# ANALOG_IO.net
KiCad netlist of a schematic drawn in Altium Designer
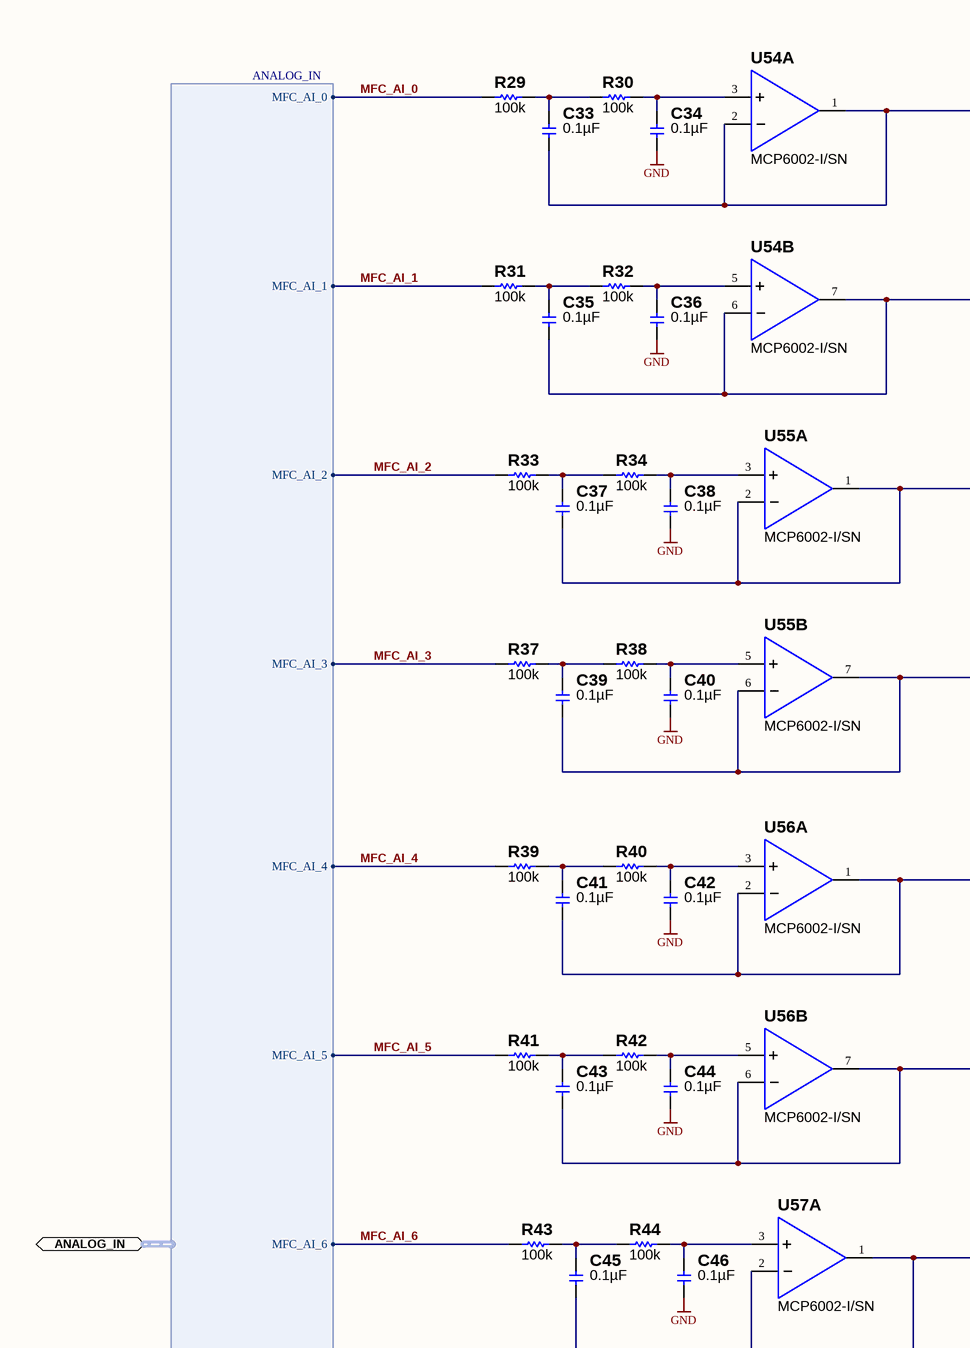
[diagram p0: ANALOG_IO.SchDoc, top left]
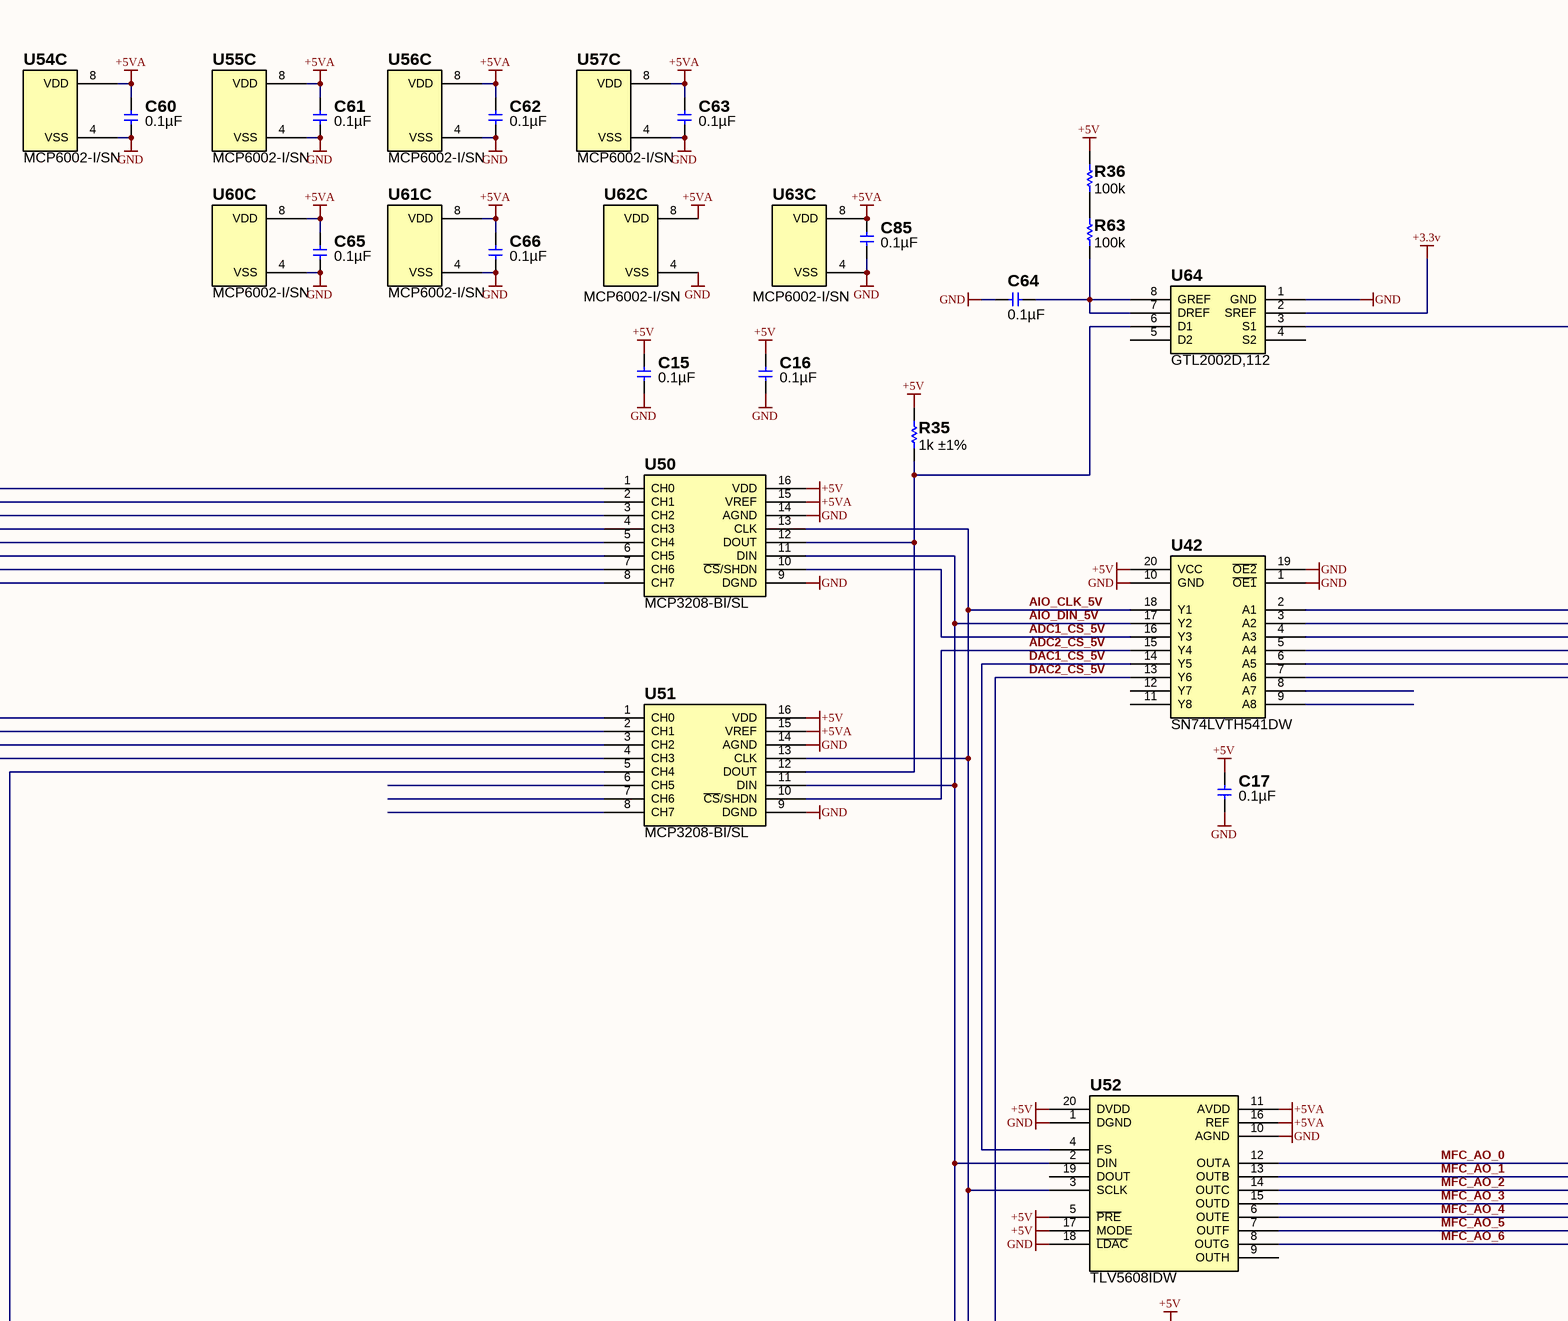
[diagram p1: ANALOG_IO.SchDoc, top middle]
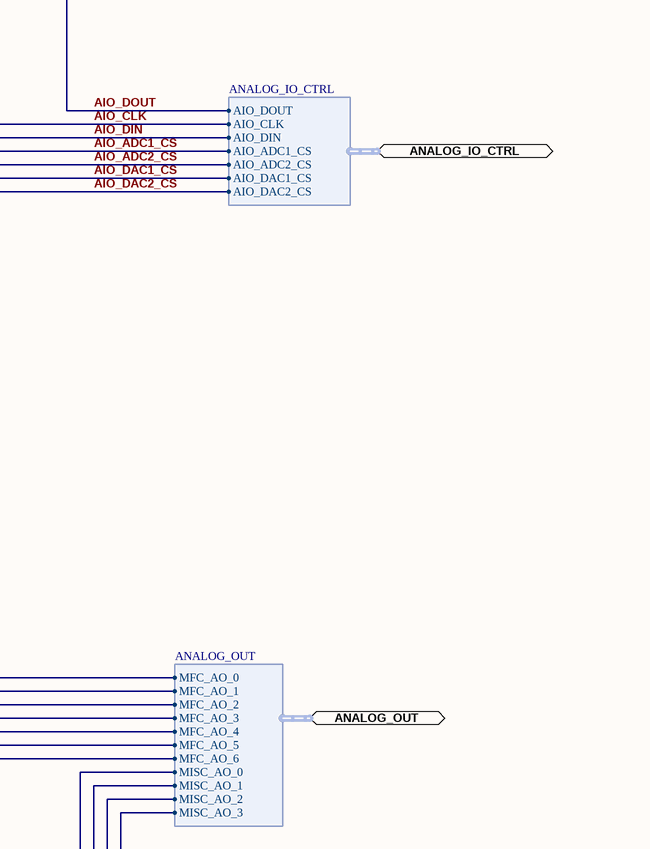
[diagram p2: ANALOG_IO.SchDoc, top right]
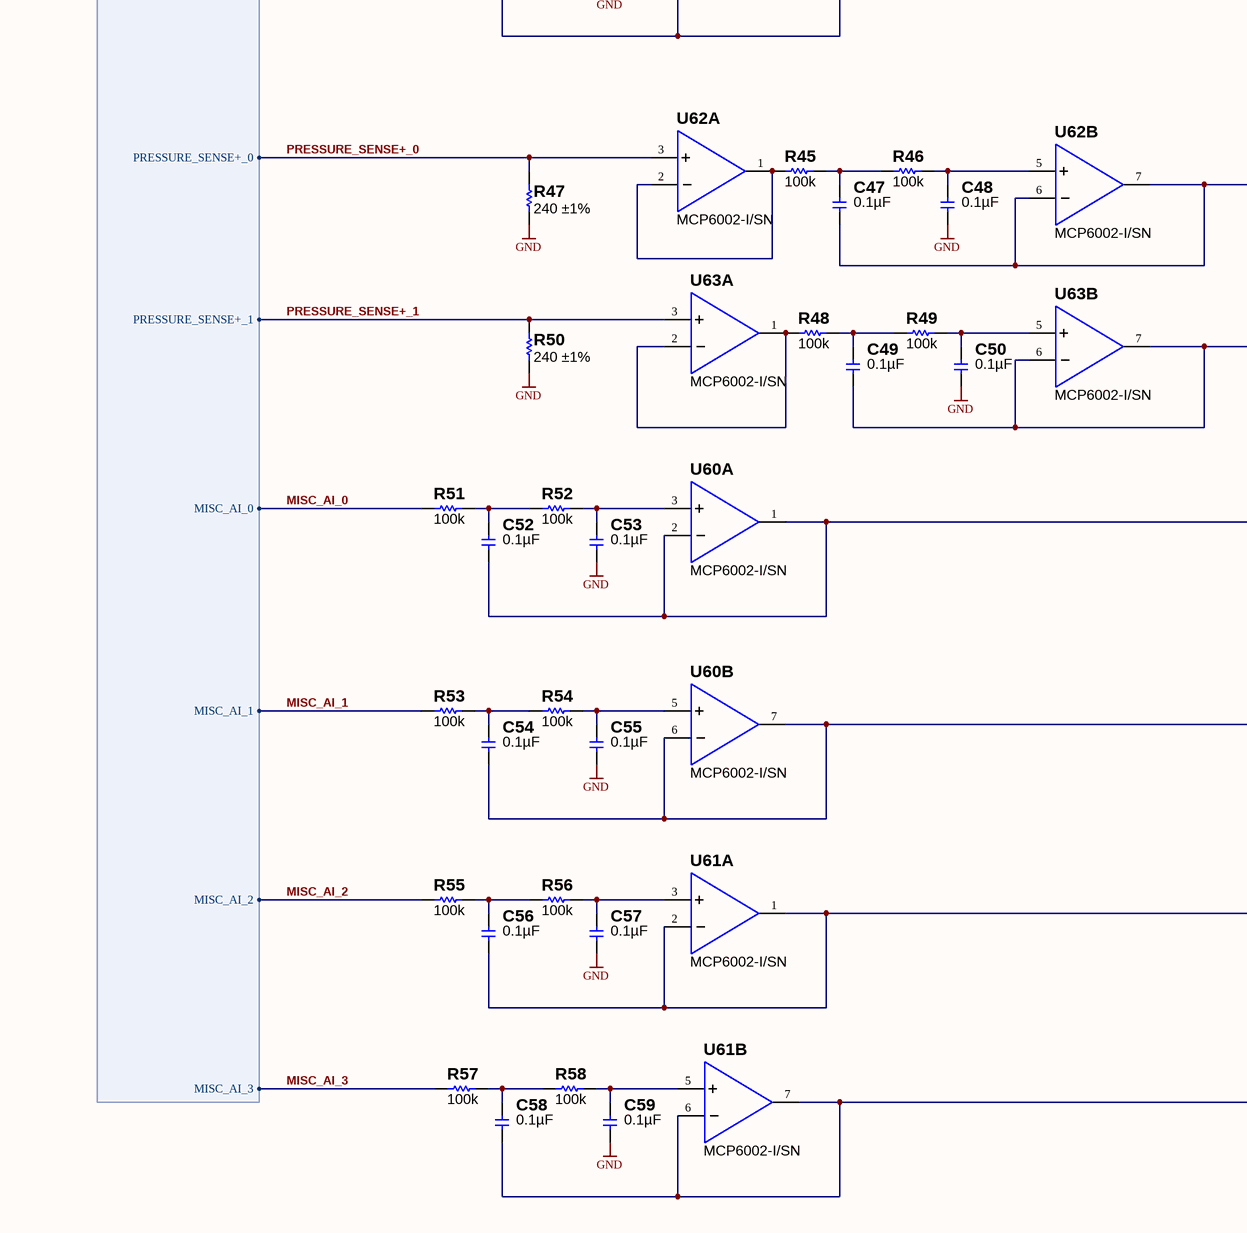
[diagram p3: ANALOG_IO.SchDoc, bottom left]
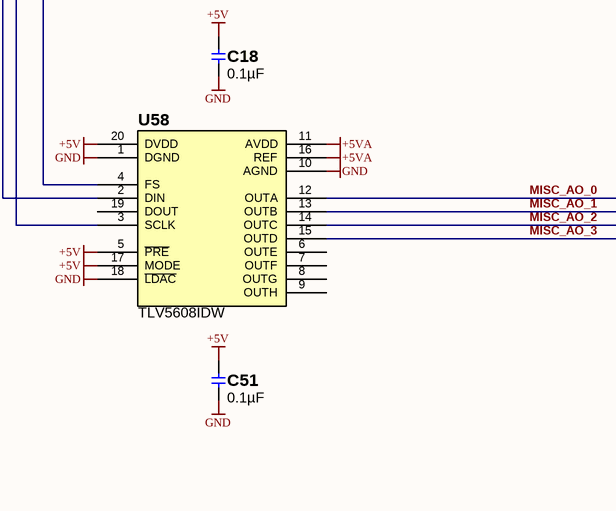
[diagram p4: ANALOG_IO.SchDoc, bottom middle]
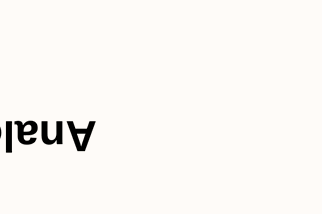
[diagram p5: ANALOG_IO.SchDoc, bottom right]

(export (version "E")
  (design (tool "Eeschema 10.0.6"))
  (components
    (comp (ref "C15")
      (value "0.1µF")
      (footprint "C0805_LD")
      (description "CAP CER 0.1UF 50V 10% X7R 0805")
      (fields
        (field (name "MANUFACTURER PART NUMBER") "GRM21BR71H104KA01L")
        (field (name "MANUFACTURER") "Murata Electronics North America")
      )
      (libsource (lib "Capacitors") (part "C_2P_NP"))
    )
    (comp (ref "C16")
      (value "0.1µF")
      (footprint "C0805_LD")
      (description "CAP CER 0.1UF 50V 10% X7R 0805")
      (fields
        (field (name "MANUFACTURER PART NUMBER") "GRM21BR71H104KA01L")
        (field (name "MANUFACTURER") "Murata Electronics North America")
      )
      (libsource (lib "Capacitors") (part "C_2P_NP"))
    )
    (comp (ref "C17")
      (value "0.1µF")
      (footprint "C0805_LD")
      (description "CAP CER 0.1UF 50V 10% X7R 0805")
      (fields
        (field (name "MANUFACTURER PART NUMBER") "GRM21BR71H104KA01L")
        (field (name "MANUFACTURER") "Murata Electronics North America")
      )
      (libsource (lib "Capacitors") (part "C_2P_NP"))
    )
    (comp (ref "C18")
      (value "0.1µF")
      (footprint "C0805_LD")
      (description "CAP CER 0.1UF 50V 10% X7R 0805")
      (fields
        (field (name "MANUFACTURER PART NUMBER") "GRM21BR71H104KA01L")
        (field (name "MANUFACTURER") "Murata Electronics North America")
      )
      (libsource (lib "Capacitors") (part "C_2P_NP"))
    )
    (comp (ref "C33")
      (value "0.1µF")
      (footprint "C0805_LD")
      (description "CAP CER 0.1UF 50V 10% X7R 0805")
      (fields
        (field (name "MANUFACTURER PART NUMBER") "GRM21BR71H104KA01L")
        (field (name "MANUFACTURER") "Murata Electronics North America")
      )
      (libsource (lib "Capacitors") (part "C_2P_NP"))
    )
    (comp (ref "C34")
      (value "0.1µF")
      (footprint "C0805_LD")
      (description "CAP CER 0.1UF 50V 10% X7R 0805")
      (fields
        (field (name "MANUFACTURER PART NUMBER") "GRM21BR71H104KA01L")
        (field (name "MANUFACTURER") "Murata Electronics North America")
      )
      (libsource (lib "Capacitors") (part "C_2P_NP"))
    )
    (comp (ref "C35")
      (value "0.1µF")
      (footprint "C0805_LD")
      (description "CAP CER 0.1UF 50V 10% X7R 0805")
      (fields
        (field (name "MANUFACTURER PART NUMBER") "GRM21BR71H104KA01L")
        (field (name "MANUFACTURER") "Murata Electronics North America")
      )
      (libsource (lib "Capacitors") (part "C_2P_NP"))
    )
    (comp (ref "C36")
      (value "0.1µF")
      (footprint "C0805_LD")
      (description "CAP CER 0.1UF 50V 10% X7R 0805")
      (fields
        (field (name "MANUFACTURER PART NUMBER") "GRM21BR71H104KA01L")
        (field (name "MANUFACTURER") "Murata Electronics North America")
      )
      (libsource (lib "Capacitors") (part "C_2P_NP"))
    )
    (comp (ref "C37")
      (value "0.1µF")
      (footprint "C0805_LD")
      (description "CAP CER 0.1UF 50V 10% X7R 0805")
      (fields
        (field (name "MANUFACTURER PART NUMBER") "GRM21BR71H104KA01L")
        (field (name "MANUFACTURER") "Murata Electronics North America")
      )
      (libsource (lib "Capacitors") (part "C_2P_NP"))
    )
    (comp (ref "C38")
      (value "0.1µF")
      (footprint "C0805_LD")
      (description "CAP CER 0.1UF 50V 10% X7R 0805")
      (fields
        (field (name "MANUFACTURER PART NUMBER") "GRM21BR71H104KA01L")
        (field (name "MANUFACTURER") "Murata Electronics North America")
      )
      (libsource (lib "Capacitors") (part "C_2P_NP"))
    )
    (comp (ref "C39")
      (value "0.1µF")
      (footprint "C0805_LD")
      (description "CAP CER 0.1UF 50V 10% X7R 0805")
      (fields
        (field (name "MANUFACTURER PART NUMBER") "GRM21BR71H104KA01L")
        (field (name "MANUFACTURER") "Murata Electronics North America")
      )
      (libsource (lib "Capacitors") (part "C_2P_NP"))
    )
    (comp (ref "C40")
      (value "0.1µF")
      (footprint "C0805_LD")
      (description "CAP CER 0.1UF 50V 10% X7R 0805")
      (fields
        (field (name "MANUFACTURER PART NUMBER") "GRM21BR71H104KA01L")
        (field (name "MANUFACTURER") "Murata Electronics North America")
      )
      (libsource (lib "Capacitors") (part "C_2P_NP"))
    )
    (comp (ref "C41")
      (value "0.1µF")
      (footprint "C0805_LD")
      (description "CAP CER 0.1UF 50V 10% X7R 0805")
      (fields
        (field (name "MANUFACTURER PART NUMBER") "GRM21BR71H104KA01L")
        (field (name "MANUFACTURER") "Murata Electronics North America")
      )
      (libsource (lib "Capacitors") (part "C_2P_NP"))
    )
    (comp (ref "C42")
      (value "0.1µF")
      (footprint "C0805_LD")
      (description "CAP CER 0.1UF 50V 10% X7R 0805")
      (fields
        (field (name "MANUFACTURER PART NUMBER") "GRM21BR71H104KA01L")
        (field (name "MANUFACTURER") "Murata Electronics North America")
      )
      (libsource (lib "Capacitors") (part "C_2P_NP"))
    )
    (comp (ref "C43")
      (value "0.1µF")
      (footprint "C0805_LD")
      (description "CAP CER 0.1UF 50V 10% X7R 0805")
      (fields
        (field (name "MANUFACTURER PART NUMBER") "GRM21BR71H104KA01L")
        (field (name "MANUFACTURER") "Murata Electronics North America")
      )
      (libsource (lib "Capacitors") (part "C_2P_NP"))
    )
    (comp (ref "C44")
      (value "0.1µF")
      (footprint "C0805_LD")
      (description "CAP CER 0.1UF 50V 10% X7R 0805")
      (fields
        (field (name "MANUFACTURER PART NUMBER") "GRM21BR71H104KA01L")
        (field (name "MANUFACTURER") "Murata Electronics North America")
      )
      (libsource (lib "Capacitors") (part "C_2P_NP"))
    )
    (comp (ref "C45")
      (value "0.1µF")
      (footprint "C0805_LD")
      (description "CAP CER 0.1UF 50V 10% X7R 0805")
      (fields
        (field (name "MANUFACTURER PART NUMBER") "GRM21BR71H104KA01L")
        (field (name "MANUFACTURER") "Murata Electronics North America")
      )
      (libsource (lib "Capacitors") (part "C_2P_NP"))
    )
    (comp (ref "C46")
      (value "0.1µF")
      (footprint "C0805_LD")
      (description "CAP CER 0.1UF 50V 10% X7R 0805")
      (fields
        (field (name "MANUFACTURER PART NUMBER") "GRM21BR71H104KA01L")
        (field (name "MANUFACTURER") "Murata Electronics North America")
      )
      (libsource (lib "Capacitors") (part "C_2P_NP"))
    )
    (comp (ref "C47")
      (value "0.1µF")
      (footprint "C0805_LD")
      (description "CAP CER 0.1UF 50V 10% X7R 0805")
      (fields
        (field (name "MANUFACTURER PART NUMBER") "GRM21BR71H104KA01L")
        (field (name "MANUFACTURER") "Murata Electronics North America")
      )
      (libsource (lib "Capacitors") (part "C_2P_NP"))
    )
    (comp (ref "C48")
      (value "0.1µF")
      (footprint "C0805_LD")
      (description "CAP CER 0.1UF 50V 10% X7R 0805")
      (fields
        (field (name "MANUFACTURER PART NUMBER") "GRM21BR71H104KA01L")
        (field (name "MANUFACTURER") "Murata Electronics North America")
      )
      (libsource (lib "Capacitors") (part "C_2P_NP"))
    )
    (comp (ref "C49")
      (value "0.1µF")
      (footprint "C0805_LD")
      (description "CAP CER 0.1UF 50V 10% X7R 0805")
      (fields
        (field (name "MANUFACTURER PART NUMBER") "GRM21BR71H104KA01L")
        (field (name "MANUFACTURER") "Murata Electronics North America")
      )
      (libsource (lib "Capacitors") (part "C_2P_NP"))
    )
    (comp (ref "C50")
      (value "0.1µF")
      (footprint "C0805_LD")
      (description "CAP CER 0.1UF 50V 10% X7R 0805")
      (fields
        (field (name "MANUFACTURER PART NUMBER") "GRM21BR71H104KA01L")
        (field (name "MANUFACTURER") "Murata Electronics North America")
      )
      (libsource (lib "Capacitors") (part "C_2P_NP"))
    )
    (comp (ref "C51")
      (value "0.1µF")
      (footprint "C0805_LD")
      (description "CAP CER 0.1UF 50V 10% X7R 0805")
      (fields
        (field (name "MANUFACTURER PART NUMBER") "GRM21BR71H104KA01L")
        (field (name "MANUFACTURER") "Murata Electronics North America")
      )
      (libsource (lib "Capacitors") (part "C_2P_NP"))
    )
    (comp (ref "C52")
      (value "0.1µF")
      (footprint "C0805_LD")
      (description "CAP CER 0.1UF 50V 10% X7R 0805")
      (fields
        (field (name "MANUFACTURER PART NUMBER") "GRM21BR71H104KA01L")
        (field (name "MANUFACTURER") "Murata Electronics North America")
      )
      (libsource (lib "Capacitors") (part "C_2P_NP"))
    )
    (comp (ref "C53")
      (value "0.1µF")
      (footprint "C0805_LD")
      (description "CAP CER 0.1UF 50V 10% X7R 0805")
      (fields
        (field (name "MANUFACTURER PART NUMBER") "GRM21BR71H104KA01L")
        (field (name "MANUFACTURER") "Murata Electronics North America")
      )
      (libsource (lib "Capacitors") (part "C_2P_NP"))
    )
    (comp (ref "C54")
      (value "0.1µF")
      (footprint "C0805_LD")
      (description "CAP CER 0.1UF 50V 10% X7R 0805")
      (fields
        (field (name "MANUFACTURER PART NUMBER") "GRM21BR71H104KA01L")
        (field (name "MANUFACTURER") "Murata Electronics North America")
      )
      (libsource (lib "Capacitors") (part "C_2P_NP"))
    )
    (comp (ref "C55")
      (value "0.1µF")
      (footprint "C0805_LD")
      (description "CAP CER 0.1UF 50V 10% X7R 0805")
      (fields
        (field (name "MANUFACTURER PART NUMBER") "GRM21BR71H104KA01L")
        (field (name "MANUFACTURER") "Murata Electronics North America")
      )
      (libsource (lib "Capacitors") (part "C_2P_NP"))
    )
    (comp (ref "C56")
      (value "0.1µF")
      (footprint "C0805_LD")
      (description "CAP CER 0.1UF 50V 10% X7R 0805")
      (fields
        (field (name "MANUFACTURER PART NUMBER") "GRM21BR71H104KA01L")
        (field (name "MANUFACTURER") "Murata Electronics North America")
      )
      (libsource (lib "Capacitors") (part "C_2P_NP"))
    )
    (comp (ref "C57")
      (value "0.1µF")
      (footprint "C0805_LD")
      (description "CAP CER 0.1UF 50V 10% X7R 0805")
      (fields
        (field (name "MANUFACTURER PART NUMBER") "GRM21BR71H104KA01L")
        (field (name "MANUFACTURER") "Murata Electronics North America")
      )
      (libsource (lib "Capacitors") (part "C_2P_NP"))
    )
    (comp (ref "C58")
      (value "0.1µF")
      (footprint "C0805_LD")
      (description "CAP CER 0.1UF 50V 10% X7R 0805")
      (fields
        (field (name "MANUFACTURER PART NUMBER") "GRM21BR71H104KA01L")
        (field (name "MANUFACTURER") "Murata Electronics North America")
      )
      (libsource (lib "Capacitors") (part "C_2P_NP"))
    )
    (comp (ref "C59")
      (value "0.1µF")
      (footprint "C0805_LD")
      (description "CAP CER 0.1UF 50V 10% X7R 0805")
      (fields
        (field (name "MANUFACTURER PART NUMBER") "GRM21BR71H104KA01L")
        (field (name "MANUFACTURER") "Murata Electronics North America")
      )
      (libsource (lib "Capacitors") (part "C_2P_NP"))
    )
    (comp (ref "C60")
      (value "0.1µF")
      (footprint "C0805_LD")
      (description "CAP CER 0.1UF 50V 10% X7R 0805")
      (fields
        (field (name "MANUFACTURER PART NUMBER") "GRM21BR71H104KA01L")
        (field (name "MANUFACTURER") "Murata Electronics North America")
      )
      (libsource (lib "Capacitors") (part "C_2P_NP"))
    )
    (comp (ref "C61")
      (value "0.1µF")
      (footprint "C0805_LD")
      (description "CAP CER 0.1UF 50V 10% X7R 0805")
      (fields
        (field (name "MANUFACTURER PART NUMBER") "GRM21BR71H104KA01L")
        (field (name "MANUFACTURER") "Murata Electronics North America")
      )
      (libsource (lib "Capacitors") (part "C_2P_NP"))
    )
    (comp (ref "C62")
      (value "0.1µF")
      (footprint "C0805_LD")
      (description "CAP CER 0.1UF 50V 10% X7R 0805")
      (fields
        (field (name "MANUFACTURER PART NUMBER") "GRM21BR71H104KA01L")
        (field (name "MANUFACTURER") "Murata Electronics North America")
      )
      (libsource (lib "Capacitors") (part "C_2P_NP"))
    )
    (comp (ref "C63")
      (value "0.1µF")
      (footprint "C0805_LD")
      (description "CAP CER 0.1UF 50V 10% X7R 0805")
      (fields
        (field (name "MANUFACTURER PART NUMBER") "GRM21BR71H104KA01L")
        (field (name "MANUFACTURER") "Murata Electronics North America")
      )
      (libsource (lib "Capacitors") (part "C_2P_NP"))
    )
    (comp (ref "C64")
      (value "0.1µF")
      (footprint "C0805_LD")
      (description "CAP CER 0.1UF 50V 10% X7R 0805")
      (fields
        (field (name "MANUFACTURER PART NUMBER") "GRM21BR71H104KA01L")
        (field (name "MANUFACTURER") "Murata Electronics North America")
      )
      (libsource (lib "Capacitors") (part "C_2P_NP"))
    )
    (comp (ref "C65")
      (value "0.1µF")
      (footprint "C0805_LD")
      (description "CAP CER 0.1UF 50V 10% X7R 0805")
      (fields
        (field (name "MANUFACTURER PART NUMBER") "GRM21BR71H104KA01L")
        (field (name "MANUFACTURER") "Murata Electronics North America")
      )
      (libsource (lib "Capacitors") (part "C_2P_NP"))
    )
    (comp (ref "C66")
      (value "0.1µF")
      (footprint "C0805_LD")
      (description "CAP CER 0.1UF 50V 10% X7R 0805")
      (fields
        (field (name "MANUFACTURER PART NUMBER") "GRM21BR71H104KA01L")
        (field (name "MANUFACTURER") "Murata Electronics North America")
      )
      (libsource (lib "Capacitors") (part "C_2P_NP"))
    )
    (comp (ref "C85")
      (value "0.1µF")
      (footprint "C0805_LD")
      (description "CAP CER 0.1UF 50V 10% X7R 0805")
      (fields
        (field (name "MANUFACTURER PART NUMBER") "GRM21BR71H104KA01L")
        (field (name "MANUFACTURER") "Murata Electronics North America")
      )
      (libsource (lib "Capacitors") (part "C_2P_NP"))
    )
    (comp (ref "R29")
      (value "100k")
      (footprint "R0805_LD")
      (description "RES 100K OHM 1/8W 1% 0805 SMD")
      (fields
        (field (name "MANUFACTURER PART NUMBER") "ERJ-6ENF1003V")
        (field (name "MANUFACTURER") "Panasonic Electronic Components")
      )
      (libsource (lib "Resistors") (part "R_2P"))
    )
    (comp (ref "R30")
      (value "100k")
      (footprint "R0805_LD")
      (description "RES 100K OHM 1/8W 1% 0805 SMD")
      (fields
        (field (name "MANUFACTURER PART NUMBER") "ERJ-6ENF1003V")
        (field (name "MANUFACTURER") "Panasonic Electronic Components")
      )
      (libsource (lib "Resistors") (part "R_2P"))
    )
    (comp (ref "R31")
      (value "100k")
      (footprint "R0805_LD")
      (description "RES 100K OHM 1/8W 1% 0805 SMD")
      (fields
        (field (name "MANUFACTURER PART NUMBER") "ERJ-6ENF1003V")
        (field (name "MANUFACTURER") "Panasonic Electronic Components")
      )
      (libsource (lib "Resistors") (part "R_2P"))
    )
    (comp (ref "R32")
      (value "100k")
      (footprint "R0805_LD")
      (description "RES 100K OHM 1/8W 1% 0805 SMD")
      (fields
        (field (name "MANUFACTURER PART NUMBER") "ERJ-6ENF1003V")
        (field (name "MANUFACTURER") "Panasonic Electronic Components")
      )
      (libsource (lib "Resistors") (part "R_2P"))
    )
    (comp (ref "R33")
      (value "100k")
      (footprint "R0805_LD")
      (description "RES 100K OHM 1/8W 1% 0805 SMD")
      (fields
        (field (name "MANUFACTURER PART NUMBER") "ERJ-6ENF1003V")
        (field (name "MANUFACTURER") "Panasonic Electronic Components")
      )
      (libsource (lib "Resistors") (part "R_2P"))
    )
    (comp (ref "R34")
      (value "100k")
      (footprint "R0805_LD")
      (description "RES 100K OHM 1/8W 1% 0805 SMD")
      (fields
        (field (name "MANUFACTURER PART NUMBER") "ERJ-6ENF1003V")
        (field (name "MANUFACTURER") "Panasonic Electronic Components")
      )
      (libsource (lib "Resistors") (part "R_2P"))
    )
    (comp (ref "R35")
      (value "1k ±1%")
      (footprint "R0805_LD")
      (description "RES 1K OHM 1/8W 1% 0805 SMD")
      (fields
        (field (name "MANUFACTURER PART NUMBER") "ERJ-6ENF1001V")
        (field (name "MANUFACTURER") "Panasonic Electronic Components")
      )
      (libsource (lib "Resistors") (part "R_2P"))
    )
    (comp (ref "R36")
      (value "100k")
      (footprint "R0805_LD")
      (description "RES 100K OHM 1/8W 1% 0805 SMD")
      (fields
        (field (name "MANUFACTURER PART NUMBER") "ERJ-6ENF1003V")
        (field (name "MANUFACTURER") "Panasonic Electronic Components")
      )
      (libsource (lib "Resistors") (part "R_2P"))
    )
    (comp (ref "R37")
      (value "100k")
      (footprint "R0805_LD")
      (description "RES 100K OHM 1/8W 1% 0805 SMD")
      (fields
        (field (name "MANUFACTURER PART NUMBER") "ERJ-6ENF1003V")
        (field (name "MANUFACTURER") "Panasonic Electronic Components")
      )
      (libsource (lib "Resistors") (part "R_2P"))
    )
    (comp (ref "R38")
      (value "100k")
      (footprint "R0805_LD")
      (description "RES 100K OHM 1/8W 1% 0805 SMD")
      (fields
        (field (name "MANUFACTURER PART NUMBER") "ERJ-6ENF1003V")
        (field (name "MANUFACTURER") "Panasonic Electronic Components")
      )
      (libsource (lib "Resistors") (part "R_2P"))
    )
    (comp (ref "R39")
      (value "100k")
      (footprint "R0805_LD")
      (description "RES 100K OHM 1/8W 1% 0805 SMD")
      (fields
        (field (name "MANUFACTURER PART NUMBER") "ERJ-6ENF1003V")
        (field (name "MANUFACTURER") "Panasonic Electronic Components")
      )
      (libsource (lib "Resistors") (part "R_2P"))
    )
    (comp (ref "R40")
      (value "100k")
      (footprint "R0805_LD")
      (description "RES 100K OHM 1/8W 1% 0805 SMD")
      (fields
        (field (name "MANUFACTURER PART NUMBER") "ERJ-6ENF1003V")
        (field (name "MANUFACTURER") "Panasonic Electronic Components")
      )
      (libsource (lib "Resistors") (part "R_2P"))
    )
    (comp (ref "R41")
      (value "100k")
      (footprint "R0805_LD")
      (description "RES 100K OHM 1/8W 1% 0805 SMD")
      (fields
        (field (name "MANUFACTURER PART NUMBER") "ERJ-6ENF1003V")
        (field (name "MANUFACTURER") "Panasonic Electronic Components")
      )
      (libsource (lib "Resistors") (part "R_2P"))
    )
    (comp (ref "R42")
      (value "100k")
      (footprint "R0805_LD")
      (description "RES 100K OHM 1/8W 1% 0805 SMD")
      (fields
        (field (name "MANUFACTURER PART NUMBER") "ERJ-6ENF1003V")
        (field (name "MANUFACTURER") "Panasonic Electronic Components")
      )
      (libsource (lib "Resistors") (part "R_2P"))
    )
    (comp (ref "R43")
      (value "100k")
      (footprint "R0805_LD")
      (description "RES 100K OHM 1/8W 1% 0805 SMD")
      (fields
        (field (name "MANUFACTURER PART NUMBER") "ERJ-6ENF1003V")
        (field (name "MANUFACTURER") "Panasonic Electronic Components")
      )
      (libsource (lib "Resistors") (part "R_2P"))
    )
    (comp (ref "R44")
      (value "100k")
      (footprint "R0805_LD")
      (description "RES 100K OHM 1/8W 1% 0805 SMD")
      (fields
        (field (name "MANUFACTURER PART NUMBER") "ERJ-6ENF1003V")
        (field (name "MANUFACTURER") "Panasonic Electronic Components")
      )
      (libsource (lib "Resistors") (part "R_2P"))
    )
    (comp (ref "R45")
      (value "100k")
      (footprint "R0805_LD")
      (description "RES 100K OHM 1/8W 1% 0805 SMD")
      (fields
        (field (name "MANUFACTURER PART NUMBER") "ERJ-6ENF1003V")
        (field (name "MANUFACTURER") "Panasonic Electronic Components")
      )
      (libsource (lib "Resistors") (part "R_2P"))
    )
    (comp (ref "R46")
      (value "100k")
      (footprint "R0805_LD")
      (description "RES 100K OHM 1/8W 1% 0805 SMD")
      (fields
        (field (name "MANUFACTURER PART NUMBER") "ERJ-6ENF1003V")
        (field (name "MANUFACTURER") "Panasonic Electronic Components")
      )
      (libsource (lib "Resistors") (part "R_2P"))
    )
    (comp (ref "R47")
      (value "240 ±1%")
      (footprint "R0805_LD")
      (description "RES 240 OHM 1/8W 1% 0805 SMD")
      (fields
        (field (name "MANUFACTURER PART NUMBER") "ERJ-6ENF2400V")
        (field (name "MANUFACTURER") "Panasonic Electronic Components")
      )
      (libsource (lib "Resistors") (part "R_2P"))
    )
    (comp (ref "R48")
      (value "100k")
      (footprint "R0805_LD")
      (description "RES 100K OHM 1/8W 1% 0805 SMD")
      (fields
        (field (name "MANUFACTURER PART NUMBER") "ERJ-6ENF1003V")
        (field (name "MANUFACTURER") "Panasonic Electronic Components")
      )
      (libsource (lib "Resistors") (part "R_2P"))
    )
    (comp (ref "R49")
      (value "100k")
      (footprint "R0805_LD")
      (description "RES 100K OHM 1/8W 1% 0805 SMD")
      (fields
        (field (name "MANUFACTURER PART NUMBER") "ERJ-6ENF1003V")
        (field (name "MANUFACTURER") "Panasonic Electronic Components")
      )
      (libsource (lib "Resistors") (part "R_2P"))
    )
    (comp (ref "R50")
      (value "240 ±1%")
      (footprint "R0805_LD")
      (description "RES 240 OHM 1/8W 1% 0805 SMD")
      (fields
        (field (name "MANUFACTURER PART NUMBER") "ERJ-6ENF2400V")
        (field (name "MANUFACTURER") "Panasonic Electronic Components")
      )
      (libsource (lib "Resistors") (part "R_2P"))
    )
    (comp (ref "R51")
      (value "100k")
      (footprint "R0805_LD")
      (description "RES 100K OHM 1/8W 1% 0805 SMD")
      (fields
        (field (name "MANUFACTURER PART NUMBER") "ERJ-6ENF1003V")
        (field (name "MANUFACTURER") "Panasonic Electronic Components")
      )
      (libsource (lib "Resistors") (part "R_2P"))
    )
    (comp (ref "R52")
      (value "100k")
      (footprint "R0805_LD")
      (description "RES 100K OHM 1/8W 1% 0805 SMD")
      (fields
        (field (name "MANUFACTURER PART NUMBER") "ERJ-6ENF1003V")
        (field (name "MANUFACTURER") "Panasonic Electronic Components")
      )
      (libsource (lib "Resistors") (part "R_2P"))
    )
    (comp (ref "R53")
      (value "100k")
      (footprint "R0805_LD")
      (description "RES 100K OHM 1/8W 1% 0805 SMD")
      (fields
        (field (name "MANUFACTURER PART NUMBER") "ERJ-6ENF1003V")
        (field (name "MANUFACTURER") "Panasonic Electronic Components")
      )
      (libsource (lib "Resistors") (part "R_2P"))
    )
    (comp (ref "R54")
      (value "100k")
      (footprint "R0805_LD")
      (description "RES 100K OHM 1/8W 1% 0805 SMD")
      (fields
        (field (name "MANUFACTURER PART NUMBER") "ERJ-6ENF1003V")
        (field (name "MANUFACTURER") "Panasonic Electronic Components")
      )
      (libsource (lib "Resistors") (part "R_2P"))
    )
    (comp (ref "R55")
      (value "100k")
      (footprint "R0805_LD")
      (description "RES 100K OHM 1/8W 1% 0805 SMD")
      (fields
        (field (name "MANUFACTURER PART NUMBER") "ERJ-6ENF1003V")
        (field (name "MANUFACTURER") "Panasonic Electronic Components")
      )
      (libsource (lib "Resistors") (part "R_2P"))
    )
    (comp (ref "R56")
      (value "100k")
      (footprint "R0805_LD")
      (description "RES 100K OHM 1/8W 1% 0805 SMD")
      (fields
        (field (name "MANUFACTURER PART NUMBER") "ERJ-6ENF1003V")
        (field (name "MANUFACTURER") "Panasonic Electronic Components")
      )
      (libsource (lib "Resistors") (part "R_2P"))
    )
    (comp (ref "R57")
      (value "100k")
      (footprint "R0805_LD")
      (description "RES 100K OHM 1/8W 1% 0805 SMD")
      (fields
        (field (name "MANUFACTURER PART NUMBER") "ERJ-6ENF1003V")
        (field (name "MANUFACTURER") "Panasonic Electronic Components")
      )
      (libsource (lib "Resistors") (part "R_2P"))
    )
    (comp (ref "R58")
      (value "100k")
      (footprint "R0805_LD")
      (description "RES 100K OHM 1/8W 1% 0805 SMD")
      (fields
        (field (name "MANUFACTURER PART NUMBER") "ERJ-6ENF1003V")
        (field (name "MANUFACTURER") "Panasonic Electronic Components")
      )
      (libsource (lib "Resistors") (part "R_2P"))
    )
    (comp (ref "R63")
      (value "100k")
      (footprint "R0805_LD")
      (description "RES 100K OHM 1/8W 1% 0805 SMD")
      (fields
        (field (name "MANUFACTURER PART NUMBER") "ERJ-6ENF1003V")
        (field (name "MANUFACTURER") "Panasonic Electronic Components")
      )
      (libsource (lib "Resistors") (part "R_2P"))
    )
    (comp (ref "U42")
      (value "SN74LVTH541DW")
      (footprint "SOIC127P1030X265-20L")
      (description "IC BUFF/DVR TRI-ST 8BIT 20SOIC")
      (fields (field (name "MANUFACTURER") "Texas Instruments"))
      (libsource (lib "eIC") (part "SN74LVTH541DW"))
    )
    (comp (ref "U50")
      (value "MCP3208-BI/SL")
      (footprint "SOIC127P600X145-16L")
      (description "IC ADC 12BIT 2.7V 8CH SPI 16SOIC")
      (fields (field (name "MANUFACTURER") "Microchip Technology"))
      (libsource (lib "eIC") (part "MCP3208-BI/SL"))
    )
    (comp (ref "U51")
      (value "MCP3208-BI/SL")
      (footprint "SOIC127P600X145-16L")
      (description "IC ADC 12BIT 2.7V 8CH SPI 16SOIC")
      (fields (field (name "MANUFACTURER") "Microchip Technology"))
      (libsource (lib "eIC") (part "MCP3208-BI/SL"))
    )
    (comp (ref "U52")
      (value "TLV5608IDW")
      (footprint "SOIC127P1030X265-20L")
      (description "IC 8 CHANNEL DAC S/O 20-SOIC")
      (fields (field (name "MANUFACTURER") "Texas Instruments"))
      (libsource (lib "eIC") (part "TLV5608IDW"))
    )
    (comp (ref "U54")
      (value "MCP6002-I/SN")
      (footprint "SOIC 8")
      (description "IC OPAMP 1.8V 1MHZ DUAL 8-SOIC")
      (fields (field (name "MANUFACTURER") "Microchip Technology"))
      (libsource (lib "eIC") (part "MCP6002-I/SN"))
    )
    (comp (ref "U55")
      (value "MCP6002-I/SN")
      (footprint "SOIC 8")
      (description "IC OPAMP 1.8V 1MHZ DUAL 8-SOIC")
      (fields (field (name "MANUFACTURER") "Microchip Technology"))
      (libsource (lib "eIC") (part "MCP6002-I/SN"))
    )
    (comp (ref "U56")
      (value "MCP6002-I/SN")
      (footprint "SOIC 8")
      (description "IC OPAMP 1.8V 1MHZ DUAL 8-SOIC")
      (fields (field (name "MANUFACTURER") "Microchip Technology"))
      (libsource (lib "eIC") (part "MCP6002-I/SN"))
    )
    (comp (ref "U57")
      (value "MCP6002-I/SN")
      (footprint "SOIC 8")
      (description "IC OPAMP 1.8V 1MHZ DUAL 8-SOIC")
      (fields (field (name "MANUFACTURER") "Microchip Technology"))
      (libsource (lib "eIC") (part "MCP6002-I/SN"))
    )
    (comp (ref "U58")
      (value "TLV5608IDW")
      (footprint "SOIC127P1030X265-20L")
      (description "IC 8 CHANNEL DAC S/O 20-SOIC")
      (fields (field (name "MANUFACTURER") "Texas Instruments"))
      (libsource (lib "eIC") (part "TLV5608IDW"))
    )
    (comp (ref "U60")
      (value "MCP6002-I/SN")
      (footprint "SOIC 8")
      (description "IC OPAMP 1.8V 1MHZ DUAL 8-SOIC")
      (fields (field (name "MANUFACTURER") "Microchip Technology"))
      (libsource (lib "eIC") (part "MCP6002-I/SN"))
    )
    (comp (ref "U61")
      (value "MCP6002-I/SN")
      (footprint "SOIC 8")
      (description "IC OPAMP 1.8V 1MHZ DUAL 8-SOIC")
      (fields (field (name "MANUFACTURER") "Microchip Technology"))
      (libsource (lib "eIC") (part "MCP6002-I/SN"))
    )
    (comp (ref "U62")
      (value "MCP6002-I/SN")
      (footprint "SOIC 8")
      (description "IC OPAMP 1.8V 1MHZ DUAL 8-SOIC")
      (fields (field (name "MANUFACTURER") "Microchip Technology"))
      (libsource (lib "eIC") (part "MCP6002-I/SN"))
    )
    (comp (ref "U63")
      (value "MCP6002-I/SN")
      (footprint "SOIC 8")
      (description "IC OPAMP 1.8V 1MHZ DUAL 8-SOIC")
      (fields (field (name "MANUFACTURER") "Microchip Technology"))
      (libsource (lib "eIC") (part "MCP6002-I/SN"))
    )
    (comp (ref "U64")
      (value "GTL2002D,112")
      (footprint "SOIC 8")
      (description "IC XLATR 2BIT BI-DIREC 8SOIC")
      (fields (field (name "MANUFACTURER") "NXP Semiconductors"))
      (libsource (lib "eIC") (part "GTL2002D,112"))
    )
  )
  (nets
    (net (code "4") (name "+3.3v") (class "Default")
      (node (ref "U64") (pin "2") (pinfunction "SREF_2") (pintype "passive"))
    )
    (net (code "5") (name "+5V") (class "Default")
      (node (ref "C15") (pin "2") (pinfunction "2_2") (pintype "passive"))
      (node (ref "C16") (pin "2") (pinfunction "2_2") (pintype "passive"))
      (node (ref "C17") (pin "2") (pinfunction "2_2") (pintype "passive"))
      (node (ref "C18") (pin "2") (pinfunction "2_2") (pintype "passive"))
      (node (ref "C51") (pin "2") (pinfunction "2_2") (pintype "passive"))
      (node (ref "R35") (pin "2") (pinfunction "2_2") (pintype "passive"))
      (node (ref "R36") (pin "2") (pinfunction "2_2") (pintype "passive"))
      (node (ref "U42") (pin "20") (pinfunction "VCC_20") (pintype "passive"))
      (node (ref "U50") (pin "16") (pinfunction "VDD_16") (pintype "passive"))
      (node (ref "U51") (pin "16") (pinfunction "VDD_16") (pintype "passive"))
      (node (ref "U52") (pin "17") (pinfunction "MODE_17") (pintype "passive"))
      (node (ref "U52") (pin "20") (pinfunction "DVDD_20") (pintype "passive"))
      (node (ref "U52") (pin "5") (pinfunction "~{PRE}_5") (pintype "passive"))
      (node (ref "U58") (pin "17") (pinfunction "MODE_17") (pintype "passive"))
      (node (ref "U58") (pin "20") (pinfunction "DVDD_20") (pintype "passive"))
      (node (ref "U58") (pin "5") (pinfunction "~{PRE}_5") (pintype "passive"))
    )
    (net (code "6") (name "+5VA") (class "Default")
      (node (ref "C60") (pin "2") (pinfunction "2_2") (pintype "passive"))
      (node (ref "C61") (pin "2") (pinfunction "2_2") (pintype "passive"))
      (node (ref "C62") (pin "2") (pinfunction "2_2") (pintype "passive"))
      (node (ref "C63") (pin "2") (pinfunction "2_2") (pintype "passive"))
      (node (ref "C65") (pin "2") (pinfunction "2_2") (pintype "passive"))
      (node (ref "C66") (pin "2") (pinfunction "2_2") (pintype "passive"))
      (node (ref "C85") (pin "2") (pinfunction "2_2") (pintype "passive"))
      (node (ref "U50") (pin "15") (pinfunction "VREF_15") (pintype "passive"))
      (node (ref "U51") (pin "15") (pinfunction "VREF_15") (pintype "passive"))
      (node (ref "U52") (pin "11") (pinfunction "AVDD_11") (pintype "passive"))
      (node (ref "U52") (pin "16") (pinfunction "REF_16") (pintype "passive"))
      (node (ref "U54") (pin "8") (pinfunction "VDD_8") (pintype "passive"))
      (node (ref "U55") (pin "8") (pinfunction "VDD_8") (pintype "passive"))
      (node (ref "U56") (pin "8") (pinfunction "VDD_8") (pintype "passive"))
      (node (ref "U57") (pin "8") (pinfunction "VDD_8") (pintype "passive"))
      (node (ref "U58") (pin "11") (pinfunction "AVDD_11") (pintype "passive"))
      (node (ref "U58") (pin "16") (pinfunction "REF_16") (pintype "passive"))
      (node (ref "U60") (pin "8") (pinfunction "VDD_8") (pintype "passive"))
      (node (ref "U61") (pin "8") (pinfunction "VDD_8") (pintype "passive"))
      (node (ref "U62") (pin "8") (pinfunction "VDD_8") (pintype "passive"))
      (node (ref "U63") (pin "8") (pinfunction "VDD_8") (pintype "passive"))
    )
    (net (code "7") (name "/ADC1_CS_5V") (class "Default")
      (node (ref "U42") (pin "16") (pinfunction "Y3_16") (pintype "passive"))
      (node (ref "U50") (pin "10") (pinfunction "~{CS}/SHDN_10") (pintype "passive"))
    )
    (net (code "8") (name "/ADC2_CS_5V") (class "Default")
      (node (ref "U42") (pin "15") (pinfunction "Y4_15") (pintype "passive"))
      (node (ref "U51") (pin "10") (pinfunction "~{CS}/SHDN_10") (pintype "passive"))
    )
    (net (code "9") (name "/AIO_ADC1_CS") (class "Default")
      (node (ref "U42") (pin "4") (pinfunction "A3_4") (pintype "passive"))
    )
    (net (code "10") (name "/AIO_ADC2_CS") (class "Default")
      (node (ref "U42") (pin "5") (pinfunction "A4_5") (pintype "passive"))
    )
    (net (code "11") (name "/AIO_CLK") (class "Default")
      (node (ref "U42") (pin "2") (pinfunction "A1_2") (pintype "passive"))
    )
    (net (code "12") (name "/AIO_CLK_5V") (class "Default")
      (node (ref "U42") (pin "18") (pinfunction "Y1_18") (pintype "passive"))
      (node (ref "U50") (pin "13") (pinfunction "CLK_13") (pintype "passive"))
      (node (ref "U51") (pin "13") (pinfunction "CLK_13") (pintype "passive"))
      (node (ref "U52") (pin "3") (pinfunction "SCLK_3") (pintype "passive"))
      (node (ref "U58") (pin "3") (pinfunction "SCLK_3") (pintype "passive"))
    )
    (net (code "13") (name "/AIO_DAC1_CS") (class "Default")
      (node (ref "U42") (pin "6") (pinfunction "A5_6") (pintype "passive"))
    )
    (net (code "14") (name "/AIO_DAC2_CS") (class "Default")
      (node (ref "U42") (pin "7") (pinfunction "A6_7") (pintype "passive"))
    )
    (net (code "15") (name "/AIO_DIN") (class "Default")
      (node (ref "U42") (pin "3") (pinfunction "A2_3") (pintype "passive"))
    )
    (net (code "16") (name "/AIO_DIN_5V") (class "Default")
      (node (ref "U42") (pin "17") (pinfunction "Y2_17") (pintype "passive"))
      (node (ref "U50") (pin "11") (pinfunction "DIN_11") (pintype "passive"))
      (node (ref "U51") (pin "11") (pinfunction "DIN_11") (pintype "passive"))
      (node (ref "U52") (pin "2") (pinfunction "DIN_2") (pintype "passive"))
      (node (ref "U58") (pin "2") (pinfunction "DIN_2") (pintype "passive"))
    )
    (net (code "17") (name "/AIO_DOUT") (class "Default")
      (node (ref "U64") (pin "3") (pinfunction "S1_3") (pintype "passive"))
    )
    (net (code "18") (name "/DAC1_CS_5V") (class "Default")
      (node (ref "U42") (pin "14") (pinfunction "Y5_14") (pintype "passive"))
      (node (ref "U52") (pin "4") (pinfunction "FS_4") (pintype "passive"))
    )
    (net (code "19") (name "/DAC2_CS_5V") (class "Default")
      (node (ref "U42") (pin "13") (pinfunction "Y6_13") (pintype "passive"))
      (node (ref "U58") (pin "4") (pinfunction "FS_4") (pintype "passive"))
    )
    (net (code "20") (name "/MFC_AI_0") (class "Default")
      (node (ref "R29") (pin "1") (pinfunction "1_1") (pintype "passive"))
    )
    (net (code "21") (name "/MFC_AI_1") (class "Default")
      (node (ref "R31") (pin "1") (pinfunction "1_1") (pintype "passive"))
    )
    (net (code "22") (name "/MFC_AI_2") (class "Default")
      (node (ref "R33") (pin "1") (pinfunction "1_1") (pintype "passive"))
    )
    (net (code "23") (name "/MFC_AI_3") (class "Default")
      (node (ref "R37") (pin "1") (pinfunction "1_1") (pintype "passive"))
    )
    (net (code "24") (name "/MFC_AI_4") (class "Default")
      (node (ref "R39") (pin "1") (pinfunction "1_1") (pintype "passive"))
    )
    (net (code "25") (name "/MFC_AI_5") (class "Default")
      (node (ref "R41") (pin "1") (pinfunction "1_1") (pintype "passive"))
    )
    (net (code "26") (name "/MFC_AI_6") (class "Default")
      (node (ref "R43") (pin "1") (pinfunction "1_1") (pintype "passive"))
    )
    (net (code "27") (name "/MFC_AO_0") (class "Default")
      (node (ref "U52") (pin "12") (pinfunction "OUTA_12") (pintype "passive"))
    )
    (net (code "28") (name "/MFC_AO_1") (class "Default")
      (node (ref "U52") (pin "13") (pinfunction "OUTB_13") (pintype "passive"))
    )
    (net (code "29") (name "/MFC_AO_2") (class "Default")
      (node (ref "U52") (pin "14") (pinfunction "OUTC_14") (pintype "passive"))
    )
    (net (code "30") (name "/MFC_AO_3") (class "Default")
      (node (ref "U52") (pin "15") (pinfunction "OUTD_15") (pintype "passive"))
    )
    (net (code "31") (name "/MFC_AO_4") (class "Default")
      (node (ref "U52") (pin "6") (pinfunction "OUTE_6") (pintype "passive"))
    )
    (net (code "32") (name "/MFC_AO_5") (class "Default")
      (node (ref "U52") (pin "7") (pinfunction "OUTF_7") (pintype "passive"))
    )
    (net (code "33") (name "/MFC_AO_6") (class "Default")
      (node (ref "U52") (pin "8") (pinfunction "OUTG_8") (pintype "passive"))
    )
    (net (code "34") (name "/MISC_AI_0") (class "Default")
      (node (ref "R51") (pin "1") (pinfunction "1_1") (pintype "passive"))
    )
    (net (code "35") (name "/MISC_AI_1") (class "Default")
      (node (ref "R53") (pin "1") (pinfunction "1_1") (pintype "passive"))
    )
    (net (code "36") (name "/MISC_AI_2") (class "Default")
      (node (ref "R55") (pin "1") (pinfunction "1_1") (pintype "passive"))
    )
    (net (code "37") (name "/MISC_AI_3") (class "Default")
      (node (ref "R57") (pin "1") (pinfunction "1_1") (pintype "passive"))
    )
    (net (code "38") (name "/MISC_AO_0") (class "Default")
      (node (ref "U58") (pin "12") (pinfunction "OUTA_12") (pintype "passive"))
    )
    (net (code "39") (name "/MISC_AO_1") (class "Default")
      (node (ref "U58") (pin "13") (pinfunction "OUTB_13") (pintype "passive"))
    )
    (net (code "40") (name "/MISC_AO_2") (class "Default")
      (node (ref "U58") (pin "14") (pinfunction "OUTC_14") (pintype "passive"))
    )
    (net (code "41") (name "/MISC_AO_3") (class "Default")
      (node (ref "U58") (pin "15") (pinfunction "OUTD_15") (pintype "passive"))
    )
    (net (code "42") (name "/PRESSURE_SENSE+_0") (class "Default")
      (node (ref "R47") (pin "2") (pinfunction "2_2") (pintype "passive"))
      (node (ref "U62") (pin "3") (pinfunction "+_3") (pintype "passive"))
    )
    (net (code "43") (name "/PRESSURE_SENSE+_1") (class "Default")
      (node (ref "R50") (pin "2") (pinfunction "2_2") (pintype "passive"))
      (node (ref "U63") (pin "3") (pinfunction "+_3") (pintype "passive"))
    )
    (net (code "47") (name "GND") (class "Default")
      (node (ref "C15") (pin "1") (pinfunction "1_1") (pintype "passive"))
      (node (ref "C16") (pin "1") (pinfunction "1_1") (pintype "passive"))
      (node (ref "C17") (pin "1") (pinfunction "1_1") (pintype "passive"))
      (node (ref "C18") (pin "1") (pinfunction "1_1") (pintype "passive"))
      (node (ref "C34") (pin "1") (pinfunction "1_1") (pintype "passive"))
      (node (ref "C36") (pin "1") (pinfunction "1_1") (pintype "passive"))
      (node (ref "C38") (pin "1") (pinfunction "1_1") (pintype "passive"))
      (node (ref "C40") (pin "1") (pinfunction "1_1") (pintype "passive"))
      (node (ref "C42") (pin "1") (pinfunction "1_1") (pintype "passive"))
      (node (ref "C44") (pin "1") (pinfunction "1_1") (pintype "passive"))
      (node (ref "C46") (pin "1") (pinfunction "1_1") (pintype "passive"))
      (node (ref "C48") (pin "1") (pinfunction "1_1") (pintype "passive"))
      (node (ref "C50") (pin "1") (pinfunction "1_1") (pintype "passive"))
      (node (ref "C51") (pin "1") (pinfunction "1_1") (pintype "passive"))
      (node (ref "C53") (pin "1") (pinfunction "1_1") (pintype "passive"))
      (node (ref "C55") (pin "1") (pinfunction "1_1") (pintype "passive"))
      (node (ref "C57") (pin "1") (pinfunction "1_1") (pintype "passive"))
      (node (ref "C59") (pin "1") (pinfunction "1_1") (pintype "passive"))
      (node (ref "C60") (pin "1") (pinfunction "1_1") (pintype "passive"))
      (node (ref "C61") (pin "1") (pinfunction "1_1") (pintype "passive"))
      (node (ref "C62") (pin "1") (pinfunction "1_1") (pintype "passive"))
      (node (ref "C63") (pin "1") (pinfunction "1_1") (pintype "passive"))
      (node (ref "C64") (pin "2") (pinfunction "2_2") (pintype "passive"))
      (node (ref "C65") (pin "1") (pinfunction "1_1") (pintype "passive"))
      (node (ref "C66") (pin "1") (pinfunction "1_1") (pintype "passive"))
      (node (ref "C85") (pin "1") (pinfunction "1_1") (pintype "passive"))
      (node (ref "R47") (pin "1") (pinfunction "1_1") (pintype "passive"))
      (node (ref "R50") (pin "1") (pinfunction "1_1") (pintype "passive"))
      (node (ref "U42") (pin "1") (pinfunction "~{OE1}_1") (pintype "passive"))
      (node (ref "U42") (pin "10") (pinfunction "GND_10") (pintype "passive"))
      (node (ref "U42") (pin "19") (pinfunction "~{OE2}_19") (pintype "passive"))
      (node (ref "U50") (pin "14") (pinfunction "AGND_14") (pintype "passive"))
      (node (ref "U50") (pin "9") (pinfunction "DGND_9") (pintype "passive"))
      (node (ref "U51") (pin "14") (pinfunction "AGND_14") (pintype "passive"))
      (node (ref "U51") (pin "9") (pinfunction "DGND_9") (pintype "passive"))
      (node (ref "U52") (pin "1") (pinfunction "DGND_1") (pintype "passive"))
      (node (ref "U52") (pin "10") (pinfunction "AGND_10") (pintype "passive"))
      (node (ref "U52") (pin "18") (pinfunction "~{LDAC}_18") (pintype "passive"))
      (node (ref "U54") (pin "4") (pinfunction "VSS_4") (pintype "passive"))
      (node (ref "U55") (pin "4") (pinfunction "VSS_4") (pintype "passive"))
      (node (ref "U56") (pin "4") (pinfunction "VSS_4") (pintype "passive"))
      (node (ref "U57") (pin "4") (pinfunction "VSS_4") (pintype "passive"))
      (node (ref "U58") (pin "1") (pinfunction "DGND_1") (pintype "passive"))
      (node (ref "U58") (pin "10") (pinfunction "AGND_10") (pintype "passive"))
      (node (ref "U58") (pin "18") (pinfunction "~{LDAC}_18") (pintype "passive"))
      (node (ref "U60") (pin "4") (pinfunction "VSS_4") (pintype "passive"))
      (node (ref "U61") (pin "4") (pinfunction "VSS_4") (pintype "passive"))
      (node (ref "U62") (pin "4") (pinfunction "VSS_4") (pintype "passive"))
      (node (ref "U63") (pin "4") (pinfunction "VSS_4") (pintype "passive"))
      (node (ref "U64") (pin "1") (pinfunction "GND_1") (pintype "passive"))
    )
    (net (code "48") (name "Net-(C33-Pad2)") (class "Default")
      (node (ref "C33") (pin "2") (pinfunction "2_2") (pintype "passive"))
      (node (ref "R29") (pin "2") (pinfunction "2_2") (pintype "passive"))
      (node (ref "R30") (pin "1") (pinfunction "1_1") (pintype "passive"))
    )
    (net (code "49") (name "Net-(C35-Pad2)") (class "Default")
      (node (ref "C35") (pin "2") (pinfunction "2_2") (pintype "passive"))
      (node (ref "R31") (pin "2") (pinfunction "2_2") (pintype "passive"))
      (node (ref "R32") (pin "1") (pinfunction "1_1") (pintype "passive"))
    )
    (net (code "50") (name "Net-(C37-Pad2)") (class "Default")
      (node (ref "C37") (pin "2") (pinfunction "2_2") (pintype "passive"))
      (node (ref "R33") (pin "2") (pinfunction "2_2") (pintype "passive"))
      (node (ref "R34") (pin "1") (pinfunction "1_1") (pintype "passive"))
    )
    (net (code "51") (name "Net-(C39-Pad2)") (class "Default")
      (node (ref "C39") (pin "2") (pinfunction "2_2") (pintype "passive"))
      (node (ref "R37") (pin "2") (pinfunction "2_2") (pintype "passive"))
      (node (ref "R38") (pin "1") (pinfunction "1_1") (pintype "passive"))
    )
    (net (code "52") (name "Net-(C41-Pad2)") (class "Default")
      (node (ref "C41") (pin "2") (pinfunction "2_2") (pintype "passive"))
      (node (ref "R39") (pin "2") (pinfunction "2_2") (pintype "passive"))
      (node (ref "R40") (pin "1") (pinfunction "1_1") (pintype "passive"))
    )
    (net (code "53") (name "Net-(C43-Pad2)") (class "Default")
      (node (ref "C43") (pin "2") (pinfunction "2_2") (pintype "passive"))
      (node (ref "R41") (pin "2") (pinfunction "2_2") (pintype "passive"))
      (node (ref "R42") (pin "1") (pinfunction "1_1") (pintype "passive"))
    )
    (net (code "54") (name "Net-(C45-Pad2)") (class "Default")
      (node (ref "C45") (pin "2") (pinfunction "2_2") (pintype "passive"))
      (node (ref "R43") (pin "2") (pinfunction "2_2") (pintype "passive"))
      (node (ref "R44") (pin "1") (pinfunction "1_1") (pintype "passive"))
    )
    (net (code "55") (name "Net-(C47-Pad2)") (class "Default")
      (node (ref "C47") (pin "2") (pinfunction "2_2") (pintype "passive"))
      (node (ref "R45") (pin "2") (pinfunction "2_2") (pintype "passive"))
      (node (ref "R46") (pin "1") (pinfunction "1_1") (pintype "passive"))
    )
    (net (code "56") (name "Net-(C49-Pad2)") (class "Default")
      (node (ref "C49") (pin "2") (pinfunction "2_2") (pintype "passive"))
      (node (ref "R48") (pin "2") (pinfunction "2_2") (pintype "passive"))
      (node (ref "R49") (pin "1") (pinfunction "1_1") (pintype "passive"))
    )
    (net (code "57") (name "Net-(C52-Pad2)") (class "Default")
      (node (ref "C52") (pin "2") (pinfunction "2_2") (pintype "passive"))
      (node (ref "R51") (pin "2") (pinfunction "2_2") (pintype "passive"))
      (node (ref "R52") (pin "1") (pinfunction "1_1") (pintype "passive"))
    )
    (net (code "58") (name "Net-(C54-Pad2)") (class "Default")
      (node (ref "C54") (pin "2") (pinfunction "2_2") (pintype "passive"))
      (node (ref "R53") (pin "2") (pinfunction "2_2") (pintype "passive"))
      (node (ref "R54") (pin "1") (pinfunction "1_1") (pintype "passive"))
    )
    (net (code "59") (name "Net-(C56-Pad2)") (class "Default")
      (node (ref "C56") (pin "2") (pinfunction "2_2") (pintype "passive"))
      (node (ref "R55") (pin "2") (pinfunction "2_2") (pintype "passive"))
      (node (ref "R56") (pin "1") (pinfunction "1_1") (pintype "passive"))
    )
    (net (code "60") (name "Net-(C58-Pad2)") (class "Default")
      (node (ref "C58") (pin "2") (pinfunction "2_2") (pintype "passive"))
      (node (ref "R57") (pin "2") (pinfunction "2_2") (pintype "passive"))
      (node (ref "R58") (pin "1") (pinfunction "1_1") (pintype "passive"))
    )
    (net (code "61") (name "Net-(R36-Pad1)") (class "Default")
      (node (ref "R36") (pin "1") (pinfunction "1_1") (pintype "passive"))
      (node (ref "R63") (pin "2") (pinfunction "2_2") (pintype "passive"))
    )
    (net (code "62") (name "Net-(U50-CH0)") (class "Default")
      (node (ref "C33") (pin "1") (pinfunction "1_1") (pintype "passive"))
      (node (ref "U50") (pin "1") (pinfunction "CH0_1") (pintype "passive"))
      (node (ref "U54") (pin "1") (pinfunction "OUT_1") (pintype "passive"))
      (node (ref "U54") (pin "2") (pinfunction "-_2") (pintype "passive"))
    )
    (net (code "63") (name "Net-(U50-CH1)") (class "Default")
      (node (ref "C35") (pin "1") (pinfunction "1_1") (pintype "passive"))
      (node (ref "U50") (pin "2") (pinfunction "CH1_2") (pintype "passive"))
      (node (ref "U54") (pin "6") (pinfunction "-_6") (pintype "passive"))
      (node (ref "U54") (pin "7") (pinfunction "OUT_7") (pintype "passive"))
    )
    (net (code "64") (name "Net-(U50-CH2)") (class "Default")
      (node (ref "C37") (pin "1") (pinfunction "1_1") (pintype "passive"))
      (node (ref "U50") (pin "3") (pinfunction "CH2_3") (pintype "passive"))
      (node (ref "U55") (pin "1") (pinfunction "OUT_1") (pintype "passive"))
      (node (ref "U55") (pin "2") (pinfunction "-_2") (pintype "passive"))
    )
    (net (code "65") (name "Net-(U50-CH3)") (class "Default")
      (node (ref "C39") (pin "1") (pinfunction "1_1") (pintype "passive"))
      (node (ref "U50") (pin "4") (pinfunction "CH3_4") (pintype "passive"))
      (node (ref "U55") (pin "6") (pinfunction "-_6") (pintype "passive"))
      (node (ref "U55") (pin "7") (pinfunction "OUT_7") (pintype "passive"))
    )
    (net (code "66") (name "Net-(U50-CH4)") (class "Default")
      (node (ref "C41") (pin "1") (pinfunction "1_1") (pintype "passive"))
      (node (ref "U50") (pin "5") (pinfunction "CH4_5") (pintype "passive"))
      (node (ref "U56") (pin "1") (pinfunction "OUT_1") (pintype "passive"))
      (node (ref "U56") (pin "2") (pinfunction "-_2") (pintype "passive"))
    )
    (net (code "67") (name "Net-(U50-CH5)") (class "Default")
      (node (ref "C43") (pin "1") (pinfunction "1_1") (pintype "passive"))
      (node (ref "U50") (pin "6") (pinfunction "CH5_6") (pintype "passive"))
      (node (ref "U56") (pin "6") (pinfunction "-_6") (pintype "passive"))
      (node (ref "U56") (pin "7") (pinfunction "OUT_7") (pintype "passive"))
    )
    (net (code "68") (name "Net-(U50-CH6)") (class "Default")
      (node (ref "C45") (pin "1") (pinfunction "1_1") (pintype "passive"))
      (node (ref "U50") (pin "7") (pinfunction "CH6_7") (pintype "passive"))
      (node (ref "U57") (pin "1") (pinfunction "OUT_1") (pintype "passive"))
      (node (ref "U57") (pin "2") (pinfunction "-_2") (pintype "passive"))
    )
    (net (code "69") (name "Net-(U50-CH7)") (class "Default")
      (node (ref "C47") (pin "1") (pinfunction "1_1") (pintype "passive"))
      (node (ref "U50") (pin "8") (pinfunction "CH7_8") (pintype "passive"))
      (node (ref "U62") (pin "6") (pinfunction "-_6") (pintype "passive"))
      (node (ref "U62") (pin "7") (pinfunction "OUT_7") (pintype "passive"))
    )
    (net (code "70") (name "Net-(U50-DOUT)") (class "Default")
      (node (ref "R35") (pin "1") (pinfunction "1_1") (pintype "passive"))
      (node (ref "U50") (pin "12") (pinfunction "DOUT_12") (pintype "passive"))
      (node (ref "U51") (pin "12") (pinfunction "DOUT_12") (pintype "passive"))
      (node (ref "U64") (pin "6") (pinfunction "D1_6") (pintype "passive"))
    )
    (net (code "71") (name "Net-(U51-CH0)") (class "Default")
      (node (ref "C49") (pin "1") (pinfunction "1_1") (pintype "passive"))
      (node (ref "U51") (pin "1") (pinfunction "CH0_1") (pintype "passive"))
      (node (ref "U63") (pin "6") (pinfunction "-_6") (pintype "passive"))
      (node (ref "U63") (pin "7") (pinfunction "OUT_7") (pintype "passive"))
    )
    (net (code "72") (name "Net-(U51-CH1)") (class "Default")
      (node (ref "C52") (pin "1") (pinfunction "1_1") (pintype "passive"))
      (node (ref "U51") (pin "2") (pinfunction "CH1_2") (pintype "passive"))
      (node (ref "U60") (pin "1") (pinfunction "OUT_1") (pintype "passive"))
      (node (ref "U60") (pin "2") (pinfunction "-_2") (pintype "passive"))
    )
    (net (code "73") (name "Net-(U51-CH2)") (class "Default")
      (node (ref "C54") (pin "1") (pinfunction "1_1") (pintype "passive"))
      (node (ref "U51") (pin "3") (pinfunction "CH2_3") (pintype "passive"))
      (node (ref "U60") (pin "6") (pinfunction "-_6") (pintype "passive"))
      (node (ref "U60") (pin "7") (pinfunction "OUT_7") (pintype "passive"))
    )
    (net (code "74") (name "Net-(U51-CH3)") (class "Default")
      (node (ref "C56") (pin "1") (pinfunction "1_1") (pintype "passive"))
      (node (ref "U51") (pin "4") (pinfunction "CH3_4") (pintype "passive"))
      (node (ref "U61") (pin "1") (pinfunction "OUT_1") (pintype "passive"))
      (node (ref "U61") (pin "2") (pinfunction "-_2") (pintype "passive"))
    )
    (net (code "75") (name "Net-(U51-CH4)") (class "Default")
      (node (ref "C58") (pin "1") (pinfunction "1_1") (pintype "passive"))
      (node (ref "U51") (pin "5") (pinfunction "CH4_5") (pintype "passive"))
      (node (ref "U61") (pin "6") (pinfunction "-_6") (pintype "passive"))
      (node (ref "U61") (pin "7") (pinfunction "OUT_7") (pintype "passive"))
    )
    (net (code "76") (name "Net-(U54A-+)") (class "Default")
      (node (ref "C34") (pin "2") (pinfunction "2_2") (pintype "passive"))
      (node (ref "R30") (pin "2") (pinfunction "2_2") (pintype "passive"))
      (node (ref "U54") (pin "3") (pinfunction "+_3") (pintype "passive"))
    )
    (net (code "77") (name "Net-(U54B-+)") (class "Default")
      (node (ref "C36") (pin "2") (pinfunction "2_2") (pintype "passive"))
      (node (ref "R32") (pin "2") (pinfunction "2_2") (pintype "passive"))
      (node (ref "U54") (pin "5") (pinfunction "+_5") (pintype "passive"))
    )
    (net (code "78") (name "Net-(U55A-+)") (class "Default")
      (node (ref "C38") (pin "2") (pinfunction "2_2") (pintype "passive"))
      (node (ref "R34") (pin "2") (pinfunction "2_2") (pintype "passive"))
      (node (ref "U55") (pin "3") (pinfunction "+_3") (pintype "passive"))
    )
    (net (code "79") (name "Net-(U55B-+)") (class "Default")
      (node (ref "C40") (pin "2") (pinfunction "2_2") (pintype "passive"))
      (node (ref "R38") (pin "2") (pinfunction "2_2") (pintype "passive"))
      (node (ref "U55") (pin "5") (pinfunction "+_5") (pintype "passive"))
    )
    (net (code "80") (name "Net-(U56A-+)") (class "Default")
      (node (ref "C42") (pin "2") (pinfunction "2_2") (pintype "passive"))
      (node (ref "R40") (pin "2") (pinfunction "2_2") (pintype "passive"))
      (node (ref "U56") (pin "3") (pinfunction "+_3") (pintype "passive"))
    )
    (net (code "81") (name "Net-(U56B-+)") (class "Default")
      (node (ref "C44") (pin "2") (pinfunction "2_2") (pintype "passive"))
      (node (ref "R42") (pin "2") (pinfunction "2_2") (pintype "passive"))
      (node (ref "U56") (pin "5") (pinfunction "+_5") (pintype "passive"))
    )
    (net (code "82") (name "Net-(U57A-+)") (class "Default")
      (node (ref "C46") (pin "2") (pinfunction "2_2") (pintype "passive"))
      (node (ref "R44") (pin "2") (pinfunction "2_2") (pintype "passive"))
      (node (ref "U57") (pin "3") (pinfunction "+_3") (pintype "passive"))
    )
    (net (code "83") (name "Net-(U60A-+)") (class "Default")
      (node (ref "C53") (pin "2") (pinfunction "2_2") (pintype "passive"))
      (node (ref "R52") (pin "2") (pinfunction "2_2") (pintype "passive"))
      (node (ref "U60") (pin "3") (pinfunction "+_3") (pintype "passive"))
    )
    (net (code "84") (name "Net-(U60B-+)") (class "Default")
      (node (ref "C55") (pin "2") (pinfunction "2_2") (pintype "passive"))
      (node (ref "R54") (pin "2") (pinfunction "2_2") (pintype "passive"))
      (node (ref "U60") (pin "5") (pinfunction "+_5") (pintype "passive"))
    )
    (net (code "85") (name "Net-(U61A-+)") (class "Default")
      (node (ref "C57") (pin "2") (pinfunction "2_2") (pintype "passive"))
      (node (ref "R56") (pin "2") (pinfunction "2_2") (pintype "passive"))
      (node (ref "U61") (pin "3") (pinfunction "+_3") (pintype "passive"))
    )
    (net (code "86") (name "Net-(U61B-+)") (class "Default")
      (node (ref "C59") (pin "2") (pinfunction "2_2") (pintype "passive"))
      (node (ref "R58") (pin "2") (pinfunction "2_2") (pintype "passive"))
      (node (ref "U61") (pin "5") (pinfunction "+_5") (pintype "passive"))
    )
    (net (code "87") (name "Net-(U62A--)") (class "Default")
      (node (ref "R45") (pin "1") (pinfunction "1_1") (pintype "passive"))
      (node (ref "U62") (pin "1") (pinfunction "OUT_1") (pintype "passive"))
      (node (ref "U62") (pin "2") (pinfunction "-_2") (pintype "passive"))
    )
    (net (code "88") (name "Net-(U62B-+)") (class "Default")
      (node (ref "C48") (pin "2") (pinfunction "2_2") (pintype "passive"))
      (node (ref "R46") (pin "2") (pinfunction "2_2") (pintype "passive"))
      (node (ref "U62") (pin "5") (pinfunction "+_5") (pintype "passive"))
    )
    (net (code "89") (name "Net-(U63A--)") (class "Default")
      (node (ref "R48") (pin "1") (pinfunction "1_1") (pintype "passive"))
      (node (ref "U63") (pin "1") (pinfunction "OUT_1") (pintype "passive"))
      (node (ref "U63") (pin "2") (pinfunction "-_2") (pintype "passive"))
    )
    (net (code "90") (name "Net-(U63B-+)") (class "Default")
      (node (ref "C50") (pin "2") (pinfunction "2_2") (pintype "passive"))
      (node (ref "R49") (pin "2") (pinfunction "2_2") (pintype "passive"))
      (node (ref "U63") (pin "5") (pinfunction "+_5") (pintype "passive"))
    )
    (net (code "91") (name "Net-(U64-DREF)") (class "Default")
      (node (ref "C64") (pin "1") (pinfunction "1_1") (pintype "passive"))
      (node (ref "R63") (pin "1") (pinfunction "1_1") (pintype "passive"))
      (node (ref "U64") (pin "7") (pinfunction "DREF_7") (pintype "passive"))
      (node (ref "U64") (pin "8") (pinfunction "GREF_8") (pintype "passive"))
    )
    (net (code "92") (name "unconnected-(U42-A7-Pad8)") (class "Default")
      (node (ref "U42") (pin "8") (pinfunction "A7_8") (pintype "passive"))
    )
    (net (code "93") (name "unconnected-(U42-A8-Pad9)") (class "Default")
      (node (ref "U42") (pin "9") (pinfunction "A8_9") (pintype "passive"))
    )
    (net (code "94") (name "unconnected-(U42-Y7-Pad12)") (class "Default")
      (node (ref "U42") (pin "12") (pinfunction "Y7_12") (pintype "passive"))
    )
    (net (code "95") (name "unconnected-(U42-Y8-Pad11)") (class "Default")
      (node (ref "U42") (pin "11") (pinfunction "Y8_11") (pintype "passive"))
    )
    (net (code "96") (name "unconnected-(U51-CH5-Pad6)") (class "Default")
      (node (ref "U51") (pin "6") (pinfunction "CH5_6") (pintype "passive"))
    )
    (net (code "97") (name "unconnected-(U51-CH6-Pad7)") (class "Default")
      (node (ref "U51") (pin "7") (pinfunction "CH6_7") (pintype "passive"))
    )
    (net (code "98") (name "unconnected-(U51-CH7-Pad8)") (class "Default")
      (node (ref "U51") (pin "8") (pinfunction "CH7_8") (pintype "passive"))
    )
    (net (code "99") (name "unconnected-(U52-DOUT-Pad19)") (class "Default")
      (node (ref "U52") (pin "19") (pinfunction "DOUT_19") (pintype "passive"))
    )
    (net (code "100") (name "unconnected-(U52-OUTH-Pad9)") (class "Default")
      (node (ref "U52") (pin "9") (pinfunction "OUTH_9") (pintype "passive"))
    )
    (net (code "101") (name "unconnected-(U58-DOUT-Pad19)") (class "Default")
      (node (ref "U58") (pin "19") (pinfunction "DOUT_19") (pintype "passive"))
    )
    (net (code "102") (name "unconnected-(U58-OUTE-Pad6)") (class "Default")
      (node (ref "U58") (pin "6") (pinfunction "OUTE_6") (pintype "passive"))
    )
    (net (code "103") (name "unconnected-(U58-OUTF-Pad7)") (class "Default")
      (node (ref "U58") (pin "7") (pinfunction "OUTF_7") (pintype "passive"))
    )
    (net (code "104") (name "unconnected-(U58-OUTG-Pad8)") (class "Default")
      (node (ref "U58") (pin "8") (pinfunction "OUTG_8") (pintype "passive"))
    )
    (net (code "105") (name "unconnected-(U58-OUTH-Pad9)") (class "Default")
      (node (ref "U58") (pin "9") (pinfunction "OUTH_9") (pintype "passive"))
    )
    (net (code "106") (name "unconnected-(U64-D2-Pad5)") (class "Default")
      (node (ref "U64") (pin "5") (pinfunction "D2_5") (pintype "passive"))
    )
    (net (code "107") (name "unconnected-(U64-S2-Pad4)") (class "Default")
      (node (ref "U64") (pin "4") (pinfunction "S2_4") (pintype "passive"))
    )
  )
)
